# LED_Button.net
KiCad netlist of a schematic drawn in Altium Designer
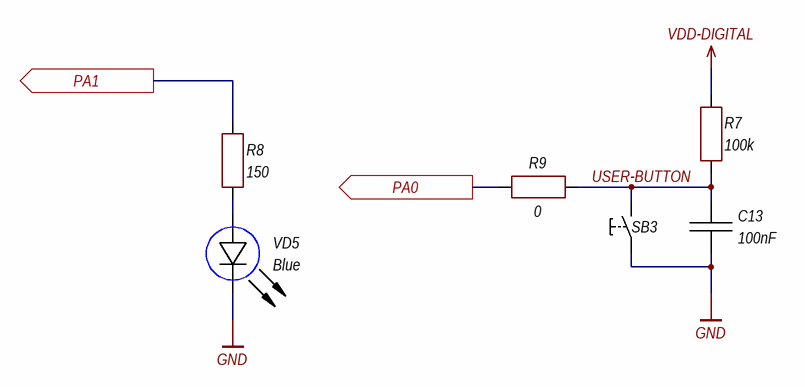
[diagram p0: LED&Button.SchDoc]

(export (version "E")
  (design (tool "Eeschema 10.0.6"))
  (components
    (comp (ref "C13") (value "100nF") (footprint "CH0402C") (libsource (lib "Discrete") (part "Capacitor")))
    (comp (ref "R7") (value "100k") (footprint "CH0402R") (libsource (lib "Discrete") (part "Resistor")))
    (comp (ref "R8") (value "150") (footprint "CH0402R") (libsource (lib "Discrete") (part "Resistor")))
    (comp (ref "R9") (value "0") (footprint "CH0402R") (libsource (lib "") (part "Resistor_1")))
    (comp (ref "SB3")
      (value "\"Кнопка\"")
      (footprint "BUT: YTS-A017")
      (description "Button, no latching")
      (libsource (lib "Connectors") (part "1-Button"))
    )
    (comp (ref "VD5") (value "Blue") (footprint "CH0402LG") (libsource (lib "Discrete") (part "LED")))
  )
  (nets
    (net (code "1") (name "/PA0") (class "Default")
      (node (ref "R9") (pin "1") (pinfunction "1_1") (pintype "passive"))
    )
    (net (code "2") (name "/PA1") (class "Default")
      (node (ref "R8") (pin "2") (pinfunction "2_2") (pintype "passive"))
    )
    (net (code "3") (name "/USER-BUTTON") (class "Default")
      (node (ref "C13") (pin "2") (pinfunction "2_2") (pintype "passive"))
      (node (ref "R7") (pin "1") (pinfunction "1_1") (pintype "passive"))
      (node (ref "R9") (pin "2") (pinfunction "2_2") (pintype "passive"))
      (node (ref "SB3") (pin "2") (pinfunction "2_2") (pintype "passive"))
    )
    (net (code "4") (name "GND") (class "Default")
      (node (ref "C13") (pin "1") (pinfunction "1_1") (pintype "passive"))
      (node (ref "SB3") (pin "1") (pinfunction "1_1") (pintype "passive"))
      (node (ref "VD5") (pin "2") (pinfunction "C_2") (pintype "passive"))
    )
    (net (code "5") (name "Net-(VD5-A)") (class "Default")
      (node (ref "R8") (pin "1") (pinfunction "1_1") (pintype "passive"))
      (node (ref "VD5") (pin "1") (pinfunction "A_1") (pintype "passive"))
    )
    (net (code "6") (name "VDD-DIGITAL") (class "Default")
      (node (ref "R7") (pin "2") (pinfunction "2_2") (pintype "passive"))
    )
  )
)
